# Impedance_converter.net
KiCad netlist of a schematic drawn in Altium Designer
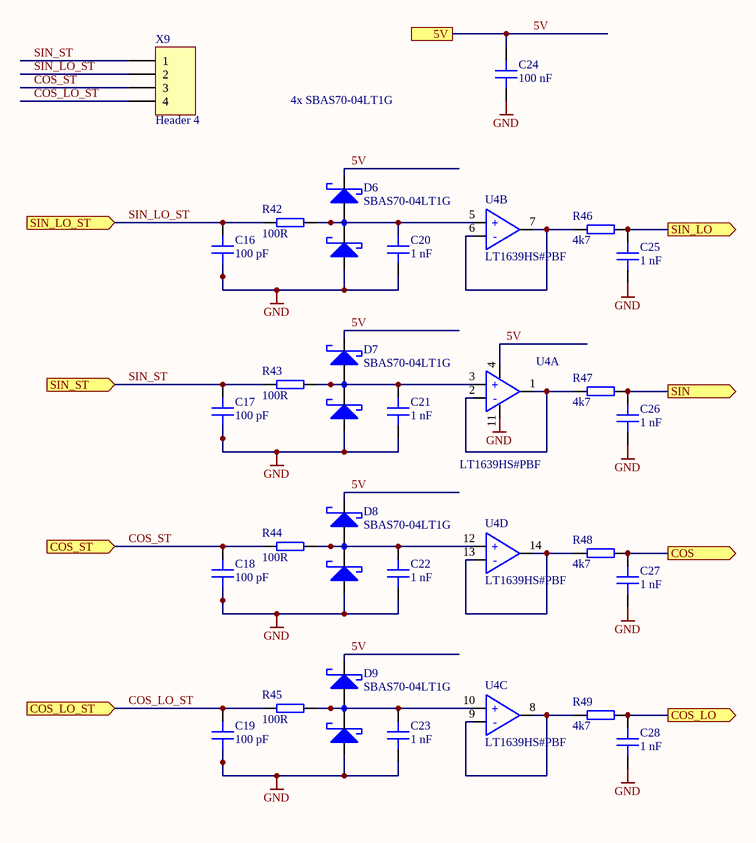
[diagram p0: Impedance converter.SchDoc]

(export (version "E")
  (design (tool "Eeschema 10.0.6"))
  (components
    (comp (ref "C16")
      (value "100 pF")
      (footprint "C_0603")
      (description "50V 100pF C0G ±5% 0603 Multilayer Ceramic Capacitors MLCC - SMD/SMT ROHS")
      (fields
        (field (name "MANUFACTURER PART NUMBER") "CL10C101JB8NNNC")
        (field (name "MANUFACTURER") "Samsung Electro-Mechanics")
        (field (name "CREATED FROM") "AGeiger")
      )
      (libsource (lib "user") (part "Capacitor"))
    )
    (comp (ref "C17")
      (value "100 pF")
      (footprint "C_0603")
      (description "50V 100pF C0G ±5% 0603 Multilayer Ceramic Capacitors MLCC - SMD/SMT ROHS")
      (fields
        (field (name "MANUFACTURER PART NUMBER") "CL10C101JB8NNNC")
        (field (name "MANUFACTURER") "Samsung Electro-Mechanics")
        (field (name "CREATED FROM") "AGeiger")
      )
      (libsource (lib "user") (part "Capacitor"))
    )
    (comp (ref "C18")
      (value "100 pF")
      (footprint "C_0603")
      (description "50V 100pF C0G ±5% 0603 Multilayer Ceramic Capacitors MLCC - SMD/SMT ROHS")
      (fields
        (field (name "MANUFACTURER PART NUMBER") "CL10C101JB8NNNC")
        (field (name "MANUFACTURER") "Samsung Electro-Mechanics")
        (field (name "CREATED FROM") "AGeiger")
      )
      (libsource (lib "user") (part "Capacitor"))
    )
    (comp (ref "C19")
      (value "100 pF")
      (footprint "C_0603")
      (description "50V 100pF C0G ±5% 0603 Multilayer Ceramic Capacitors MLCC - SMD/SMT ROHS")
      (fields
        (field (name "MANUFACTURER PART NUMBER") "CL10C101JB8NNNC")
        (field (name "MANUFACTURER") "Samsung Electro-Mechanics")
        (field (name "CREATED FROM") "AGeiger")
      )
      (libsource (lib "user") (part "Capacitor"))
    )
    (comp (ref "C20")
      (value "1 nF")
      (footprint "C_0603")
      (description "Capacitor 0603, 50 VDC, 1 nF, NP0")
      (fields
        (field (name "MANUFACTURER PART NUMBER") "CC0603JRNPO9BN102")
        (field (name "MANUFACTURER") "YAGEO")
        (field (name "CREATED FROM") "AGeiger")
      )
      (libsource (lib "user") (part "Capacitor"))
    )
    (comp (ref "C21")
      (value "1 nF")
      (footprint "C_0603")
      (description "Capacitor 0603, 50 VDC, 1 nF, NP0")
      (fields
        (field (name "MANUFACTURER PART NUMBER") "CC0603JRNPO9BN102")
        (field (name "MANUFACTURER") "YAGEO")
        (field (name "CREATED FROM") "AGeiger")
      )
      (libsource (lib "user") (part "Capacitor"))
    )
    (comp (ref "C22")
      (value "1 nF")
      (footprint "C_0603")
      (description "Capacitor 0603, 50 VDC, 1 nF, NP0")
      (fields
        (field (name "MANUFACTURER PART NUMBER") "CC0603JRNPO9BN102")
        (field (name "MANUFACTURER") "YAGEO")
        (field (name "CREATED FROM") "AGeiger")
      )
      (libsource (lib "user") (part "Capacitor"))
    )
    (comp (ref "C23")
      (value "1 nF")
      (footprint "C_0603")
      (description "Capacitor 0603, 50 VDC, 1 nF, NP0")
      (fields
        (field (name "MANUFACTURER PART NUMBER") "CC0603JRNPO9BN102")
        (field (name "MANUFACTURER") "YAGEO")
        (field (name "CREATED FROM") "AGeiger")
      )
      (libsource (lib "user") (part "Capacitor"))
    )
    (comp (ref "C24")
      (value "100 nF")
      (footprint "C_0603")
      (description "Capacitor 0603, 50 VDC, 100 nF, X7R")
      (fields
        (field (name "MANUFACTURER PART NUMBER") "CC0603KRX7R9BB104")
        (field (name "MANUFACTURER") "YAGEO")
        (field (name "CREATED FROM") "AGeiger")
      )
      (libsource (lib "user") (part "Capacitor"))
    )
    (comp (ref "C25")
      (value "1 nF")
      (footprint "C_0603")
      (description "Capacitor 0603, 50 VDC, 1 nF, NP0")
      (fields
        (field (name "MANUFACTURER PART NUMBER") "CC0603JRNPO9BN102")
        (field (name "MANUFACTURER") "YAGEO")
        (field (name "CREATED FROM") "AGeiger")
      )
      (libsource (lib "user") (part "Capacitor"))
    )
    (comp (ref "C26")
      (value "1 nF")
      (footprint "C_0603")
      (description "Capacitor 0603, 50 VDC, 1 nF, NP0")
      (fields
        (field (name "MANUFACTURER PART NUMBER") "CC0603JRNPO9BN102")
        (field (name "MANUFACTURER") "YAGEO")
        (field (name "CREATED FROM") "AGeiger")
      )
      (libsource (lib "user") (part "Capacitor"))
    )
    (comp (ref "C27")
      (value "1 nF")
      (footprint "C_0603")
      (description "Capacitor 0603, 50 VDC, 1 nF, NP0")
      (fields
        (field (name "MANUFACTURER PART NUMBER") "CC0603JRNPO9BN102")
        (field (name "MANUFACTURER") "YAGEO")
        (field (name "CREATED FROM") "AGeiger")
      )
      (libsource (lib "user") (part "Capacitor"))
    )
    (comp (ref "C28")
      (value "1 nF")
      (footprint "C_0603")
      (description "Capacitor 0603, 50 VDC, 1 nF, NP0")
      (fields
        (field (name "MANUFACTURER PART NUMBER") "CC0603JRNPO9BN102")
        (field (name "MANUFACTURER") "YAGEO")
        (field (name "CREATED FROM") "AGeiger")
      )
      (libsource (lib "user") (part "Capacitor"))
    )
    (comp (ref "D6")
      (value "SBAS70-04LT1G")
      (footprint "SOT-23")
      (description "DIODE SCHOTTKY 70V DUAL SOT23")
      (fields (field (name "MF") "ON Semiconductor") (field (name "LCSC PART NUMBER") "C389351"))
      (libsource (lib "Componentes_SOC") (part "Diode Array Schottky"))
    )
    (comp (ref "D7")
      (value "SBAS70-04LT1G")
      (footprint "SOT-23")
      (description "DIODE SCHOTTKY 70V DUAL SOT23")
      (fields (field (name "MF") "ON Semiconductor") (field (name "LCSC PART NUMBER") "C389351"))
      (libsource (lib "Componentes_SOC") (part "Diode Array Schottky"))
    )
    (comp (ref "D8")
      (value "SBAS70-04LT1G")
      (footprint "SOT-23")
      (description "DIODE SCHOTTKY 70V DUAL SOT23")
      (fields (field (name "MF") "ON Semiconductor") (field (name "LCSC PART NUMBER") "C389351"))
      (libsource (lib "Componentes_SOC") (part "Diode Array Schottky"))
    )
    (comp (ref "D9")
      (value "SBAS70-04LT1G")
      (footprint "SOT-23")
      (description "DIODE SCHOTTKY 70V DUAL SOT23")
      (fields (field (name "MF") "ON Semiconductor") (field (name "LCSC PART NUMBER") "C389351"))
      (libsource (lib "Componentes_SOC") (part "Diode Array Schottky"))
    )
    (comp (ref "R42")
      (value "100R")
      (footprint "RES 0603_1608")
      (description "SMD resistor E24 series")
      (fields
        (field (name "MANUFACTURER PART NUMBER") "RK73B1JTTD101J")
        (field (name "MANUFACTURER") "KOA Speer")
        (field (name "CREATED FROM") "MGremer")
      )
      (libsource (lib "user") (part "Resistor"))
    )
    (comp (ref "R43")
      (value "100R")
      (footprint "RES 0603_1608")
      (description "SMD resistor E24 series")
      (fields
        (field (name "MANUFACTURER PART NUMBER") "RK73B1JTTD101J")
        (field (name "MANUFACTURER") "KOA Speer")
        (field (name "CREATED FROM") "MGremer")
      )
      (libsource (lib "user") (part "Resistor"))
    )
    (comp (ref "R44")
      (value "100R")
      (footprint "RES 0603_1608")
      (description "SMD resistor E24 series")
      (fields
        (field (name "MANUFACTURER PART NUMBER") "RK73B1JTTD101J")
        (field (name "MANUFACTURER") "KOA Speer")
        (field (name "CREATED FROM") "MGremer")
      )
      (libsource (lib "user") (part "Resistor"))
    )
    (comp (ref "R45")
      (value "100R")
      (footprint "RES 0603_1608")
      (description "SMD resistor E24 series")
      (fields
        (field (name "MANUFACTURER PART NUMBER") "RK73B1JTTD101J")
        (field (name "MANUFACTURER") "KOA Speer")
        (field (name "CREATED FROM") "MGremer")
      )
      (libsource (lib "user") (part "Resistor"))
    )
    (comp (ref "R46")
      (value "4k7")
      (footprint "RES 0603_1608")
      (description "SMD resistor E24 series")
      (fields
        (field (name "MANUFACTURER PART NUMBER") "0603WAF4701T5E")
        (field (name "MANUFACTURER") "UNI-ROYAL")
        (field (name "CREATED FROM") "AGeiger")
      )
      (libsource (lib "user") (part "Resistor"))
    )
    (comp (ref "R47")
      (value "4k7")
      (footprint "RES 0603_1608")
      (description "SMD resistor E24 series")
      (fields
        (field (name "MANUFACTURER PART NUMBER") "0603WAF4701T5E")
        (field (name "MANUFACTURER") "UNI-ROYAL")
        (field (name "CREATED FROM") "AGeiger")
      )
      (libsource (lib "user") (part "Resistor"))
    )
    (comp (ref "R48")
      (value "4k7")
      (footprint "RES 0603_1608")
      (description "SMD resistor E24 series")
      (fields
        (field (name "MANUFACTURER PART NUMBER") "0603WAF4701T5E")
        (field (name "MANUFACTURER") "UNI-ROYAL")
        (field (name "CREATED FROM") "AGeiger")
      )
      (libsource (lib "user") (part "Resistor"))
    )
    (comp (ref "R49")
      (value "4k7")
      (footprint "RES 0603_1608")
      (description "SMD resistor E24 series")
      (fields
        (field (name "MANUFACTURER PART NUMBER") "0603WAF4701T5E")
        (field (name "MANUFACTURER") "UNI-ROYAL")
        (field (name "CREATED FROM") "AGeiger")
      )
      (libsource (lib "user") (part "Resistor"))
    )
    (comp (ref "U4")
      (value "LT1639HS#PBF")
      (footprint "SOIC-14")
      (description "IC OPAMP GP 4 CIRCUIT 14SO")
      (fields (field (name "MPN") "LT1639CS#PBF") (field (name "MF") "Analog Devices"))
      (libsource (lib "LT1639CS#PBF") (part "LT1639CS"))
    )
    (comp (ref "X9")
      (value "Header 4")
      (footprint "HDR1X4")
      (description "Header, 4-Pin")
      (fields (field (name "PUBLISHER") "Altium Limited"))
      (libsource (lib "Miscellaneous Connectors") (part "Header 4"))
    )
  )
  (nets
    (net (code "1") (name "/5V") (class "Default")
      (node (ref "C24") (pin "1") (pinfunction "1_1") (pintype "passive"))
      (node (ref "D6") (pin "2") (pintype "passive"))
      (node (ref "D7") (pin "2") (pintype "passive"))
      (node (ref "D8") (pin "2") (pintype "passive"))
      (node (ref "D9") (pin "2") (pintype "passive"))
      (node (ref "U4") (pin "4") (pinfunction "V+_4") (pintype "passive"))
    )
    (net (code "2") (name "/COS") (class "Default")
      (node (ref "C27") (pin "1") (pinfunction "1_1") (pintype "passive"))
      (node (ref "R48") (pin "2") (pinfunction "2_2") (pintype "passive"))
    )
    (net (code "3") (name "/COS_LO") (class "Default")
      (node (ref "C28") (pin "1") (pinfunction "1_1") (pintype "passive"))
      (node (ref "R49") (pin "2") (pinfunction "2_2") (pintype "passive"))
    )
    (net (code "4") (name "/COS_LO_ST") (class "Default")
      (node (ref "C19") (pin "1") (pinfunction "1_1") (pintype "passive"))
      (node (ref "R45") (pin "1") (pinfunction "1_1") (pintype "passive"))
      (node (ref "X9") (pin "4") (pinfunction "4_4") (pintype "passive"))
    )
    (net (code "5") (name "/COS_ST") (class "Default")
      (node (ref "C18") (pin "1") (pinfunction "1_1") (pintype "passive"))
      (node (ref "R44") (pin "1") (pinfunction "1_1") (pintype "passive"))
      (node (ref "X9") (pin "3") (pinfunction "3_3") (pintype "passive"))
    )
    (net (code "6") (name "/SIN") (class "Default")
      (node (ref "C26") (pin "1") (pinfunction "1_1") (pintype "passive"))
      (node (ref "R47") (pin "2") (pinfunction "2_2") (pintype "passive"))
    )
    (net (code "7") (name "/SIN_LO") (class "Default")
      (node (ref "C25") (pin "1") (pinfunction "1_1") (pintype "passive"))
      (node (ref "R46") (pin "2") (pinfunction "2_2") (pintype "passive"))
    )
    (net (code "8") (name "/SIN_LO_ST") (class "Default")
      (node (ref "C16") (pin "1") (pinfunction "1_1") (pintype "passive"))
      (node (ref "R42") (pin "1") (pinfunction "1_1") (pintype "passive"))
      (node (ref "X9") (pin "2") (pinfunction "2_2") (pintype "passive"))
    )
    (net (code "9") (name "/SIN_ST") (class "Default")
      (node (ref "C17") (pin "1") (pinfunction "1_1") (pintype "passive"))
      (node (ref "R43") (pin "1") (pinfunction "1_1") (pintype "passive"))
      (node (ref "X9") (pin "1") (pinfunction "1_1") (pintype "passive"))
    )
    (net (code "10") (name "GND") (class "Default")
      (node (ref "C16") (pin "2") (pinfunction "2_2") (pintype "passive"))
      (node (ref "C17") (pin "2") (pinfunction "2_2") (pintype "passive"))
      (node (ref "C18") (pin "2") (pinfunction "2_2") (pintype "passive"))
      (node (ref "C19") (pin "2") (pinfunction "2_2") (pintype "passive"))
      (node (ref "C20") (pin "2") (pinfunction "2_2") (pintype "passive"))
      (node (ref "C21") (pin "2") (pinfunction "2_2") (pintype "passive"))
      (node (ref "C22") (pin "2") (pinfunction "2_2") (pintype "passive"))
      (node (ref "C23") (pin "2") (pinfunction "2_2") (pintype "passive"))
      (node (ref "C24") (pin "2") (pinfunction "2_2") (pintype "passive"))
      (node (ref "C25") (pin "2") (pinfunction "2_2") (pintype "passive"))
      (node (ref "C26") (pin "2") (pinfunction "2_2") (pintype "passive"))
      (node (ref "C27") (pin "2") (pinfunction "2_2") (pintype "passive"))
      (node (ref "C28") (pin "2") (pinfunction "2_2") (pintype "passive"))
      (node (ref "D6") (pin "1") (pintype "passive"))
      (node (ref "D7") (pin "1") (pintype "passive"))
      (node (ref "D8") (pin "1") (pintype "passive"))
      (node (ref "D9") (pin "1") (pintype "passive"))
      (node (ref "U4") (pin "11") (pinfunction "V-_11") (pintype "passive"))
    )
    (net (code "11") (name "Net-(U4A-+)") (class "Default")
      (node (ref "C21") (pin "1") (pinfunction "1_1") (pintype "passive"))
      (node (ref "D7") (pin "3") (pintype "passive"))
      (node (ref "R43") (pin "2") (pinfunction "2_2") (pintype "passive"))
      (node (ref "U4") (pin "3") (pinfunction "+_3") (pintype "passive"))
    )
    (net (code "12") (name "Net-(U4A--)") (class "Default")
      (node (ref "R47") (pin "1") (pinfunction "1_1") (pintype "passive"))
      (node (ref "U4") (pin "1") (pintype "passive"))
      (node (ref "U4") (pin "2") (pinfunction "-_2") (pintype "passive"))
    )
    (net (code "13") (name "Net-(U4B-+)") (class "Default")
      (node (ref "C20") (pin "1") (pinfunction "1_1") (pintype "passive"))
      (node (ref "D6") (pin "3") (pintype "passive"))
      (node (ref "R42") (pin "2") (pinfunction "2_2") (pintype "passive"))
      (node (ref "U4") (pin "5") (pinfunction "+_5") (pintype "passive"))
    )
    (net (code "14") (name "Net-(U4B--)") (class "Default")
      (node (ref "R46") (pin "1") (pinfunction "1_1") (pintype "passive"))
      (node (ref "U4") (pin "6") (pinfunction "-_6") (pintype "passive"))
      (node (ref "U4") (pin "7") (pintype "passive"))
    )
    (net (code "15") (name "Net-(U4C-+)") (class "Default")
      (node (ref "C23") (pin "1") (pinfunction "1_1") (pintype "passive"))
      (node (ref "D9") (pin "3") (pintype "passive"))
      (node (ref "R45") (pin "2") (pinfunction "2_2") (pintype "passive"))
      (node (ref "U4") (pin "10") (pinfunction "+_10") (pintype "passive"))
    )
    (net (code "16") (name "Net-(U4C--)") (class "Default")
      (node (ref "R49") (pin "1") (pinfunction "1_1") (pintype "passive"))
      (node (ref "U4") (pin "8") (pintype "passive"))
      (node (ref "U4") (pin "9") (pinfunction "-_9") (pintype "passive"))
    )
    (net (code "17") (name "Net-(U4D-+)") (class "Default")
      (node (ref "C22") (pin "1") (pinfunction "1_1") (pintype "passive"))
      (node (ref "D8") (pin "3") (pintype "passive"))
      (node (ref "R44") (pin "2") (pinfunction "2_2") (pintype "passive"))
      (node (ref "U4") (pin "12") (pinfunction "+_12") (pintype "passive"))
    )
    (net (code "18") (name "Net-(U4D--)") (class "Default")
      (node (ref "R48") (pin "1") (pinfunction "1_1") (pintype "passive"))
      (node (ref "U4") (pin "13") (pinfunction "-_13") (pintype "passive"))
      (node (ref "U4") (pin "14") (pintype "passive"))
    )
  )
)
